# dist_board.net
KiCad netlist of a schematic drawn in EAGLE
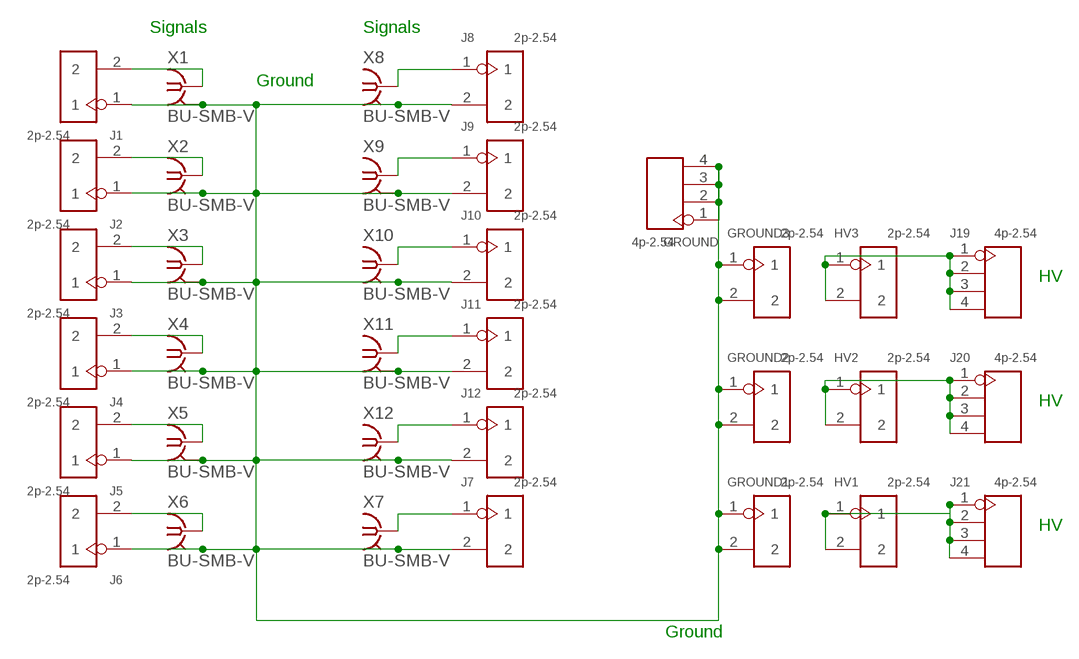
[diagram p0: schematic, sheet 1]

(export (version "E")
  (design (tool "Eeschema 10.0.6"))
  (components
    (comp (ref "GROUND")
      (value "4p-2.54")
      (footprint "eagle-import:H4-2.54")
      (fields (field (name "MPN") "F185-1104A1BSYA1"))
      (libsource (lib "eagle-import") (part "DIP-BLACK-FEMALE-HEADER-VERT(4P-2.54)"))
    )
    (comp (ref "GROUND1")
      (value "2p-2.54")
      (footprint "eagle-import:H2-2.54")
      (fields (field (name "MPN") "P125-1102A0BS116A1"))
      (libsource (lib "eagle-import") (part "DIP-BLACK-MALE-HEADER-VERT(2P-2.54)"))
    )
    (comp (ref "GROUND2")
      (value "2p-2.54")
      (footprint "eagle-import:H2-2.54")
      (fields (field (name "MPN") "P125-1102A0BS116A1"))
      (libsource (lib "eagle-import") (part "DIP-BLACK-MALE-HEADER-VERT(2P-2.54)"))
    )
    (comp (ref "GROUND3")
      (value "2p-2.54")
      (footprint "eagle-import:H2-2.54")
      (fields (field (name "MPN") "P125-1102A0BS116A1"))
      (libsource (lib "eagle-import") (part "DIP-BLACK-MALE-HEADER-VERT(2P-2.54)"))
    )
    (comp (ref "HV1")
      (value "2p-2.54")
      (footprint "eagle-import:H2-2.54")
      (fields (field (name "MPN") "P125-1102A0BS116A1"))
      (libsource (lib "eagle-import") (part "DIP-BLACK-MALE-HEADER-VERT(2P-2.54)"))
    )
    (comp (ref "HV2")
      (value "2p-2.54")
      (footprint "eagle-import:H2-2.54")
      (fields (field (name "MPN") "P125-1102A0BS116A1"))
      (libsource (lib "eagle-import") (part "DIP-BLACK-MALE-HEADER-VERT(2P-2.54)"))
    )
    (comp (ref "HV3")
      (value "2p-2.54")
      (footprint "eagle-import:H2-2.54")
      (fields (field (name "MPN") "P125-1102A0BS116A1"))
      (libsource (lib "eagle-import") (part "DIP-BLACK-MALE-HEADER-VERT(2P-2.54)"))
    )
    (comp (ref "J1")
      (value "2p-2.54")
      (footprint "eagle-import:H2-2.54")
      (fields (field (name "MPN") "P125-1102A0BS116A1"))
      (libsource (lib "eagle-import") (part "DIP-BLACK-MALE-HEADER-VERT(2P-2.54)"))
    )
    (comp (ref "J2")
      (value "2p-2.54")
      (footprint "eagle-import:H2-2.54")
      (fields (field (name "MPN") "P125-1102A0BS116A1"))
      (libsource (lib "eagle-import") (part "DIP-BLACK-MALE-HEADER-VERT(2P-2.54)"))
    )
    (comp (ref "J3")
      (value "2p-2.54")
      (footprint "eagle-import:H2-2.54")
      (fields (field (name "MPN") "P125-1102A0BS116A1"))
      (libsource (lib "eagle-import") (part "DIP-BLACK-MALE-HEADER-VERT(2P-2.54)"))
    )
    (comp (ref "J4")
      (value "2p-2.54")
      (footprint "eagle-import:H2-2.54")
      (fields (field (name "MPN") "P125-1102A0BS116A1"))
      (libsource (lib "eagle-import") (part "DIP-BLACK-MALE-HEADER-VERT(2P-2.54)"))
    )
    (comp (ref "J5")
      (value "2p-2.54")
      (footprint "eagle-import:H2-2.54")
      (fields (field (name "MPN") "P125-1102A0BS116A1"))
      (libsource (lib "eagle-import") (part "DIP-BLACK-MALE-HEADER-VERT(2P-2.54)"))
    )
    (comp (ref "J6")
      (value "2p-2.54")
      (footprint "eagle-import:H2-2.54")
      (fields (field (name "MPN") "P125-1102A0BS116A1"))
      (libsource (lib "eagle-import") (part "DIP-BLACK-MALE-HEADER-VERT(2P-2.54)"))
    )
    (comp (ref "J7")
      (value "2p-2.54")
      (footprint "eagle-import:H2-2.54")
      (fields (field (name "MPN") "P125-1102A0BS116A1"))
      (libsource (lib "eagle-import") (part "DIP-BLACK-MALE-HEADER-VERT(2P-2.54)"))
    )
    (comp (ref "J8")
      (value "2p-2.54")
      (footprint "eagle-import:H2-2.54")
      (fields (field (name "MPN") "P125-1102A0BS116A1"))
      (libsource (lib "eagle-import") (part "DIP-BLACK-MALE-HEADER-VERT(2P-2.54)"))
    )
    (comp (ref "J9")
      (value "2p-2.54")
      (footprint "eagle-import:H2-2.54")
      (fields (field (name "MPN") "P125-1102A0BS116A1"))
      (libsource (lib "eagle-import") (part "DIP-BLACK-MALE-HEADER-VERT(2P-2.54)"))
    )
    (comp (ref "J10")
      (value "2p-2.54")
      (footprint "eagle-import:H2-2.54")
      (fields (field (name "MPN") "P125-1102A0BS116A1"))
      (libsource (lib "eagle-import") (part "DIP-BLACK-MALE-HEADER-VERT(2P-2.54)"))
    )
    (comp (ref "J11")
      (value "2p-2.54")
      (footprint "eagle-import:H2-2.54")
      (fields (field (name "MPN") "P125-1102A0BS116A1"))
      (libsource (lib "eagle-import") (part "DIP-BLACK-MALE-HEADER-VERT(2P-2.54)"))
    )
    (comp (ref "J12")
      (value "2p-2.54")
      (footprint "eagle-import:H2-2.54")
      (fields (field (name "MPN") "P125-1102A0BS116A1"))
      (libsource (lib "eagle-import") (part "DIP-BLACK-MALE-HEADER-VERT(2P-2.54)"))
    )
    (comp (ref "J19")
      (value "4p-2.54")
      (footprint "eagle-import:H4-2.54")
      (fields (field (name "MPN") "F185-1104A1BSYA1"))
      (libsource (lib "eagle-import") (part "DIP-BLACK-FEMALE-HEADER-VERT(4P-2.54)"))
    )
    (comp (ref "J20")
      (value "4p-2.54")
      (footprint "eagle-import:H4-2.54")
      (fields (field (name "MPN") "F185-1104A1BSYA1"))
      (libsource (lib "eagle-import") (part "DIP-BLACK-FEMALE-HEADER-VERT(4P-2.54)"))
    )
    (comp (ref "J21")
      (value "4p-2.54")
      (footprint "eagle-import:H4-2.54")
      (fields (field (name "MPN") "F185-1104A1BSYA1"))
      (libsource (lib "eagle-import") (part "DIP-BLACK-FEMALE-HEADER-VERT(4P-2.54)"))
    )
    (comp (ref "X1")
      (value "BU-SMB-V")
      (footprint "eagle-import:BU-SMB-V")
      (libsource (lib "eagle-import") (part "BU-SMB-V"))
    )
    (comp (ref "X2")
      (value "BU-SMB-V")
      (footprint "eagle-import:BU-SMB-V")
      (libsource (lib "eagle-import") (part "BU-SMB-V"))
    )
    (comp (ref "X3")
      (value "BU-SMB-V")
      (footprint "eagle-import:BU-SMB-V")
      (libsource (lib "eagle-import") (part "BU-SMB-V"))
    )
    (comp (ref "X4")
      (value "BU-SMB-V")
      (footprint "eagle-import:BU-SMB-V")
      (libsource (lib "eagle-import") (part "BU-SMB-V"))
    )
    (comp (ref "X5")
      (value "BU-SMB-V")
      (footprint "eagle-import:BU-SMB-V")
      (libsource (lib "eagle-import") (part "BU-SMB-V"))
    )
    (comp (ref "X6")
      (value "BU-SMB-V")
      (footprint "eagle-import:BU-SMB-V")
      (libsource (lib "eagle-import") (part "BU-SMB-V"))
    )
    (comp (ref "X7")
      (value "BU-SMB-V")
      (footprint "eagle-import:BU-SMB-V")
      (libsource (lib "eagle-import") (part "BU-SMB-V"))
    )
    (comp (ref "X8")
      (value "BU-SMB-V")
      (footprint "eagle-import:BU-SMB-V")
      (libsource (lib "eagle-import") (part "BU-SMB-V"))
    )
    (comp (ref "X9")
      (value "BU-SMB-V")
      (footprint "eagle-import:BU-SMB-V")
      (libsource (lib "eagle-import") (part "BU-SMB-V"))
    )
    (comp (ref "X10")
      (value "BU-SMB-V")
      (footprint "eagle-import:BU-SMB-V")
      (libsource (lib "eagle-import") (part "BU-SMB-V"))
    )
    (comp (ref "X11")
      (value "BU-SMB-V")
      (footprint "eagle-import:BU-SMB-V")
      (libsource (lib "eagle-import") (part "BU-SMB-V"))
    )
    (comp (ref "X12")
      (value "BU-SMB-V")
      (footprint "eagle-import:BU-SMB-V")
      (libsource (lib "eagle-import") (part "BU-SMB-V"))
    )
  )
  (nets
    (net (code "1") (name "Net-(GROUND-P$1)") (class "Default")
      (node (ref "GROUND") (pin "1") (pinfunction "P$1_1") (pintype "bidirectional"))
      (node (ref "GROUND") (pin "2") (pinfunction "P$2_2") (pintype "bidirectional"))
      (node (ref "GROUND") (pin "3") (pinfunction "P$3_3") (pintype "bidirectional"))
      (node (ref "GROUND") (pin "4") (pinfunction "P$4_4") (pintype "bidirectional"))
      (node (ref "GROUND1") (pin "1") (pinfunction "1_1") (pintype "bidirectional"))
      (node (ref "GROUND1") (pin "2") (pinfunction "2_2") (pintype "bidirectional"))
      (node (ref "GROUND2") (pin "1") (pinfunction "1_1") (pintype "bidirectional"))
      (node (ref "GROUND2") (pin "2") (pinfunction "2_2") (pintype "bidirectional"))
      (node (ref "GROUND3") (pin "1") (pinfunction "1_1") (pintype "bidirectional"))
      (node (ref "GROUND3") (pin "2") (pinfunction "2_2") (pintype "bidirectional"))
      (node (ref "J1") (pin "1") (pinfunction "1_1") (pintype "bidirectional"))
      (node (ref "J10") (pin "2") (pinfunction "2_2") (pintype "bidirectional"))
      (node (ref "J11") (pin "2") (pinfunction "2_2") (pintype "bidirectional"))
      (node (ref "J12") (pin "2") (pinfunction "2_2") (pintype "bidirectional"))
      (node (ref "J2") (pin "1") (pinfunction "1_1") (pintype "bidirectional"))
      (node (ref "J3") (pin "1") (pinfunction "1_1") (pintype "bidirectional"))
      (node (ref "J4") (pin "1") (pinfunction "1_1") (pintype "bidirectional"))
      (node (ref "J5") (pin "1") (pinfunction "1_1") (pintype "bidirectional"))
      (node (ref "J6") (pin "1") (pinfunction "1_1") (pintype "bidirectional"))
      (node (ref "J7") (pin "2") (pinfunction "2_2") (pintype "bidirectional"))
      (node (ref "J8") (pin "2") (pinfunction "2_2") (pintype "bidirectional"))
      (node (ref "J9") (pin "2") (pinfunction "2_2") (pintype "bidirectional"))
      (node (ref "X1") (pin "2") (pinfunction "2_2") (pintype "passive"))
      (node (ref "X1") (pin "3") (pinfunction "2_3") (pintype "passive"))
      (node (ref "X1") (pin "4") (pinfunction "2_4") (pintype "passive"))
      (node (ref "X1") (pin "5") (pinfunction "2_5") (pintype "passive"))
      (node (ref "X10") (pin "2") (pinfunction "2_2") (pintype "passive"))
      (node (ref "X10") (pin "3") (pinfunction "2_3") (pintype "passive"))
      (node (ref "X10") (pin "4") (pinfunction "2_4") (pintype "passive"))
      (node (ref "X10") (pin "5") (pinfunction "2_5") (pintype "passive"))
      (node (ref "X11") (pin "2") (pinfunction "2_2") (pintype "passive"))
      (node (ref "X11") (pin "3") (pinfunction "2_3") (pintype "passive"))
      (node (ref "X11") (pin "4") (pinfunction "2_4") (pintype "passive"))
      (node (ref "X11") (pin "5") (pinfunction "2_5") (pintype "passive"))
      (node (ref "X12") (pin "2") (pinfunction "2_2") (pintype "passive"))
      (node (ref "X12") (pin "3") (pinfunction "2_3") (pintype "passive"))
      (node (ref "X12") (pin "4") (pinfunction "2_4") (pintype "passive"))
      (node (ref "X12") (pin "5") (pinfunction "2_5") (pintype "passive"))
      (node (ref "X2") (pin "2") (pinfunction "2_2") (pintype "passive"))
      (node (ref "X2") (pin "3") (pinfunction "2_3") (pintype "passive"))
      (node (ref "X2") (pin "4") (pinfunction "2_4") (pintype "passive"))
      (node (ref "X2") (pin "5") (pinfunction "2_5") (pintype "passive"))
      (node (ref "X3") (pin "2") (pinfunction "2_2") (pintype "passive"))
      (node (ref "X3") (pin "3") (pinfunction "2_3") (pintype "passive"))
      (node (ref "X3") (pin "4") (pinfunction "2_4") (pintype "passive"))
      (node (ref "X3") (pin "5") (pinfunction "2_5") (pintype "passive"))
      (node (ref "X4") (pin "2") (pinfunction "2_2") (pintype "passive"))
      (node (ref "X4") (pin "3") (pinfunction "2_3") (pintype "passive"))
      (node (ref "X4") (pin "4") (pinfunction "2_4") (pintype "passive"))
      (node (ref "X4") (pin "5") (pinfunction "2_5") (pintype "passive"))
      (node (ref "X5") (pin "2") (pinfunction "2_2") (pintype "passive"))
      (node (ref "X5") (pin "3") (pinfunction "2_3") (pintype "passive"))
      (node (ref "X5") (pin "4") (pinfunction "2_4") (pintype "passive"))
      (node (ref "X5") (pin "5") (pinfunction "2_5") (pintype "passive"))
      (node (ref "X6") (pin "2") (pinfunction "2_2") (pintype "passive"))
      (node (ref "X6") (pin "3") (pinfunction "2_3") (pintype "passive"))
      (node (ref "X6") (pin "4") (pinfunction "2_4") (pintype "passive"))
      (node (ref "X6") (pin "5") (pinfunction "2_5") (pintype "passive"))
      (node (ref "X7") (pin "2") (pinfunction "2_2") (pintype "passive"))
      (node (ref "X7") (pin "3") (pinfunction "2_3") (pintype "passive"))
      (node (ref "X7") (pin "4") (pinfunction "2_4") (pintype "passive"))
      (node (ref "X7") (pin "5") (pinfunction "2_5") (pintype "passive"))
      (node (ref "X8") (pin "2") (pinfunction "2_2") (pintype "passive"))
      (node (ref "X8") (pin "3") (pinfunction "2_3") (pintype "passive"))
      (node (ref "X8") (pin "4") (pinfunction "2_4") (pintype "passive"))
      (node (ref "X8") (pin "5") (pinfunction "2_5") (pintype "passive"))
      (node (ref "X9") (pin "2") (pinfunction "2_2") (pintype "passive"))
      (node (ref "X9") (pin "3") (pinfunction "2_3") (pintype "passive"))
      (node (ref "X9") (pin "4") (pinfunction "2_4") (pintype "passive"))
      (node (ref "X9") (pin "5") (pinfunction "2_5") (pintype "passive"))
    )
    (net (code "2") (name "Net-(J1-Pad2)") (class "Default")
      (node (ref "J1") (pin "2") (pinfunction "2_2") (pintype "bidirectional"))
      (node (ref "X1") (pin "1") (pinfunction "1_1") (pintype "passive"))
    )
    (net (code "3") (name "Net-(J2-Pad2)") (class "Default")
      (node (ref "J2") (pin "2") (pinfunction "2_2") (pintype "bidirectional"))
      (node (ref "X2") (pin "1") (pinfunction "1_1") (pintype "passive"))
    )
    (net (code "4") (name "Net-(J3-Pad2)") (class "Default")
      (node (ref "J3") (pin "2") (pinfunction "2_2") (pintype "bidirectional"))
      (node (ref "X3") (pin "1") (pinfunction "1_1") (pintype "passive"))
    )
    (net (code "5") (name "Net-(J4-Pad2)") (class "Default")
      (node (ref "J4") (pin "2") (pinfunction "2_2") (pintype "bidirectional"))
      (node (ref "X4") (pin "1") (pinfunction "1_1") (pintype "passive"))
    )
    (net (code "6") (name "Net-(J5-Pad2)") (class "Default")
      (node (ref "J5") (pin "2") (pinfunction "2_2") (pintype "bidirectional"))
      (node (ref "X5") (pin "1") (pinfunction "1_1") (pintype "passive"))
    )
    (net (code "7") (name "Net-(J6-Pad2)") (class "Default")
      (node (ref "J6") (pin "2") (pinfunction "2_2") (pintype "bidirectional"))
      (node (ref "X6") (pin "1") (pinfunction "1_1") (pintype "passive"))
    )
    (net (code "8") (name "Net-(J7-Pad1)") (class "Default")
      (node (ref "J7") (pin "1") (pinfunction "1_1") (pintype "bidirectional"))
      (node (ref "X7") (pin "1") (pinfunction "1_1") (pintype "passive"))
    )
    (net (code "9") (name "Net-(J8-Pad1)") (class "Default")
      (node (ref "J8") (pin "1") (pinfunction "1_1") (pintype "bidirectional"))
      (node (ref "X8") (pin "1") (pinfunction "1_1") (pintype "passive"))
    )
    (net (code "10") (name "Net-(J9-Pad1)") (class "Default")
      (node (ref "J9") (pin "1") (pinfunction "1_1") (pintype "bidirectional"))
      (node (ref "X9") (pin "1") (pinfunction "1_1") (pintype "passive"))
    )
    (net (code "11") (name "Net-(J10-Pad1)") (class "Default")
      (node (ref "J10") (pin "1") (pinfunction "1_1") (pintype "bidirectional"))
      (node (ref "X10") (pin "1") (pinfunction "1_1") (pintype "passive"))
    )
    (net (code "12") (name "Net-(J11-Pad1)") (class "Default")
      (node (ref "J11") (pin "1") (pinfunction "1_1") (pintype "bidirectional"))
      (node (ref "X11") (pin "1") (pinfunction "1_1") (pintype "passive"))
    )
    (net (code "13") (name "Net-(J12-Pad1)") (class "Default")
      (node (ref "J12") (pin "1") (pinfunction "1_1") (pintype "bidirectional"))
      (node (ref "X12") (pin "1") (pinfunction "1_1") (pintype "passive"))
    )
    (net (code "14") (name "Net-(J19-P$1)") (class "Default")
      (node (ref "HV3") (pin "1") (pinfunction "1_1") (pintype "bidirectional"))
      (node (ref "HV3") (pin "2") (pinfunction "2_2") (pintype "bidirectional"))
      (node (ref "J19") (pin "1") (pinfunction "P$1_1") (pintype "bidirectional"))
      (node (ref "J19") (pin "2") (pinfunction "P$2_2") (pintype "bidirectional"))
      (node (ref "J19") (pin "3") (pinfunction "P$3_3") (pintype "bidirectional"))
      (node (ref "J19") (pin "4") (pinfunction "P$4_4") (pintype "bidirectional"))
    )
    (net (code "15") (name "Net-(J20-P$1)") (class "Default")
      (node (ref "HV2") (pin "1") (pinfunction "1_1") (pintype "bidirectional"))
      (node (ref "HV2") (pin "2") (pinfunction "2_2") (pintype "bidirectional"))
      (node (ref "J20") (pin "1") (pinfunction "P$1_1") (pintype "bidirectional"))
      (node (ref "J20") (pin "2") (pinfunction "P$2_2") (pintype "bidirectional"))
      (node (ref "J20") (pin "3") (pinfunction "P$3_3") (pintype "bidirectional"))
      (node (ref "J20") (pin "4") (pinfunction "P$4_4") (pintype "bidirectional"))
    )
    (net (code "16") (name "Net-(J21-P$1)") (class "Default")
      (node (ref "HV1") (pin "1") (pinfunction "1_1") (pintype "bidirectional"))
      (node (ref "HV1") (pin "2") (pinfunction "2_2") (pintype "bidirectional"))
      (node (ref "J21") (pin "1") (pinfunction "P$1_1") (pintype "bidirectional"))
      (node (ref "J21") (pin "2") (pinfunction "P$2_2") (pintype "bidirectional"))
      (node (ref "J21") (pin "3") (pinfunction "P$3_3") (pintype "bidirectional"))
      (node (ref "J21") (pin "4") (pinfunction "P$4_4") (pintype "bidirectional"))
    )
  )
)
